# koppelpunkt.net
KiCad netlist of a schematic drawn in EAGLE
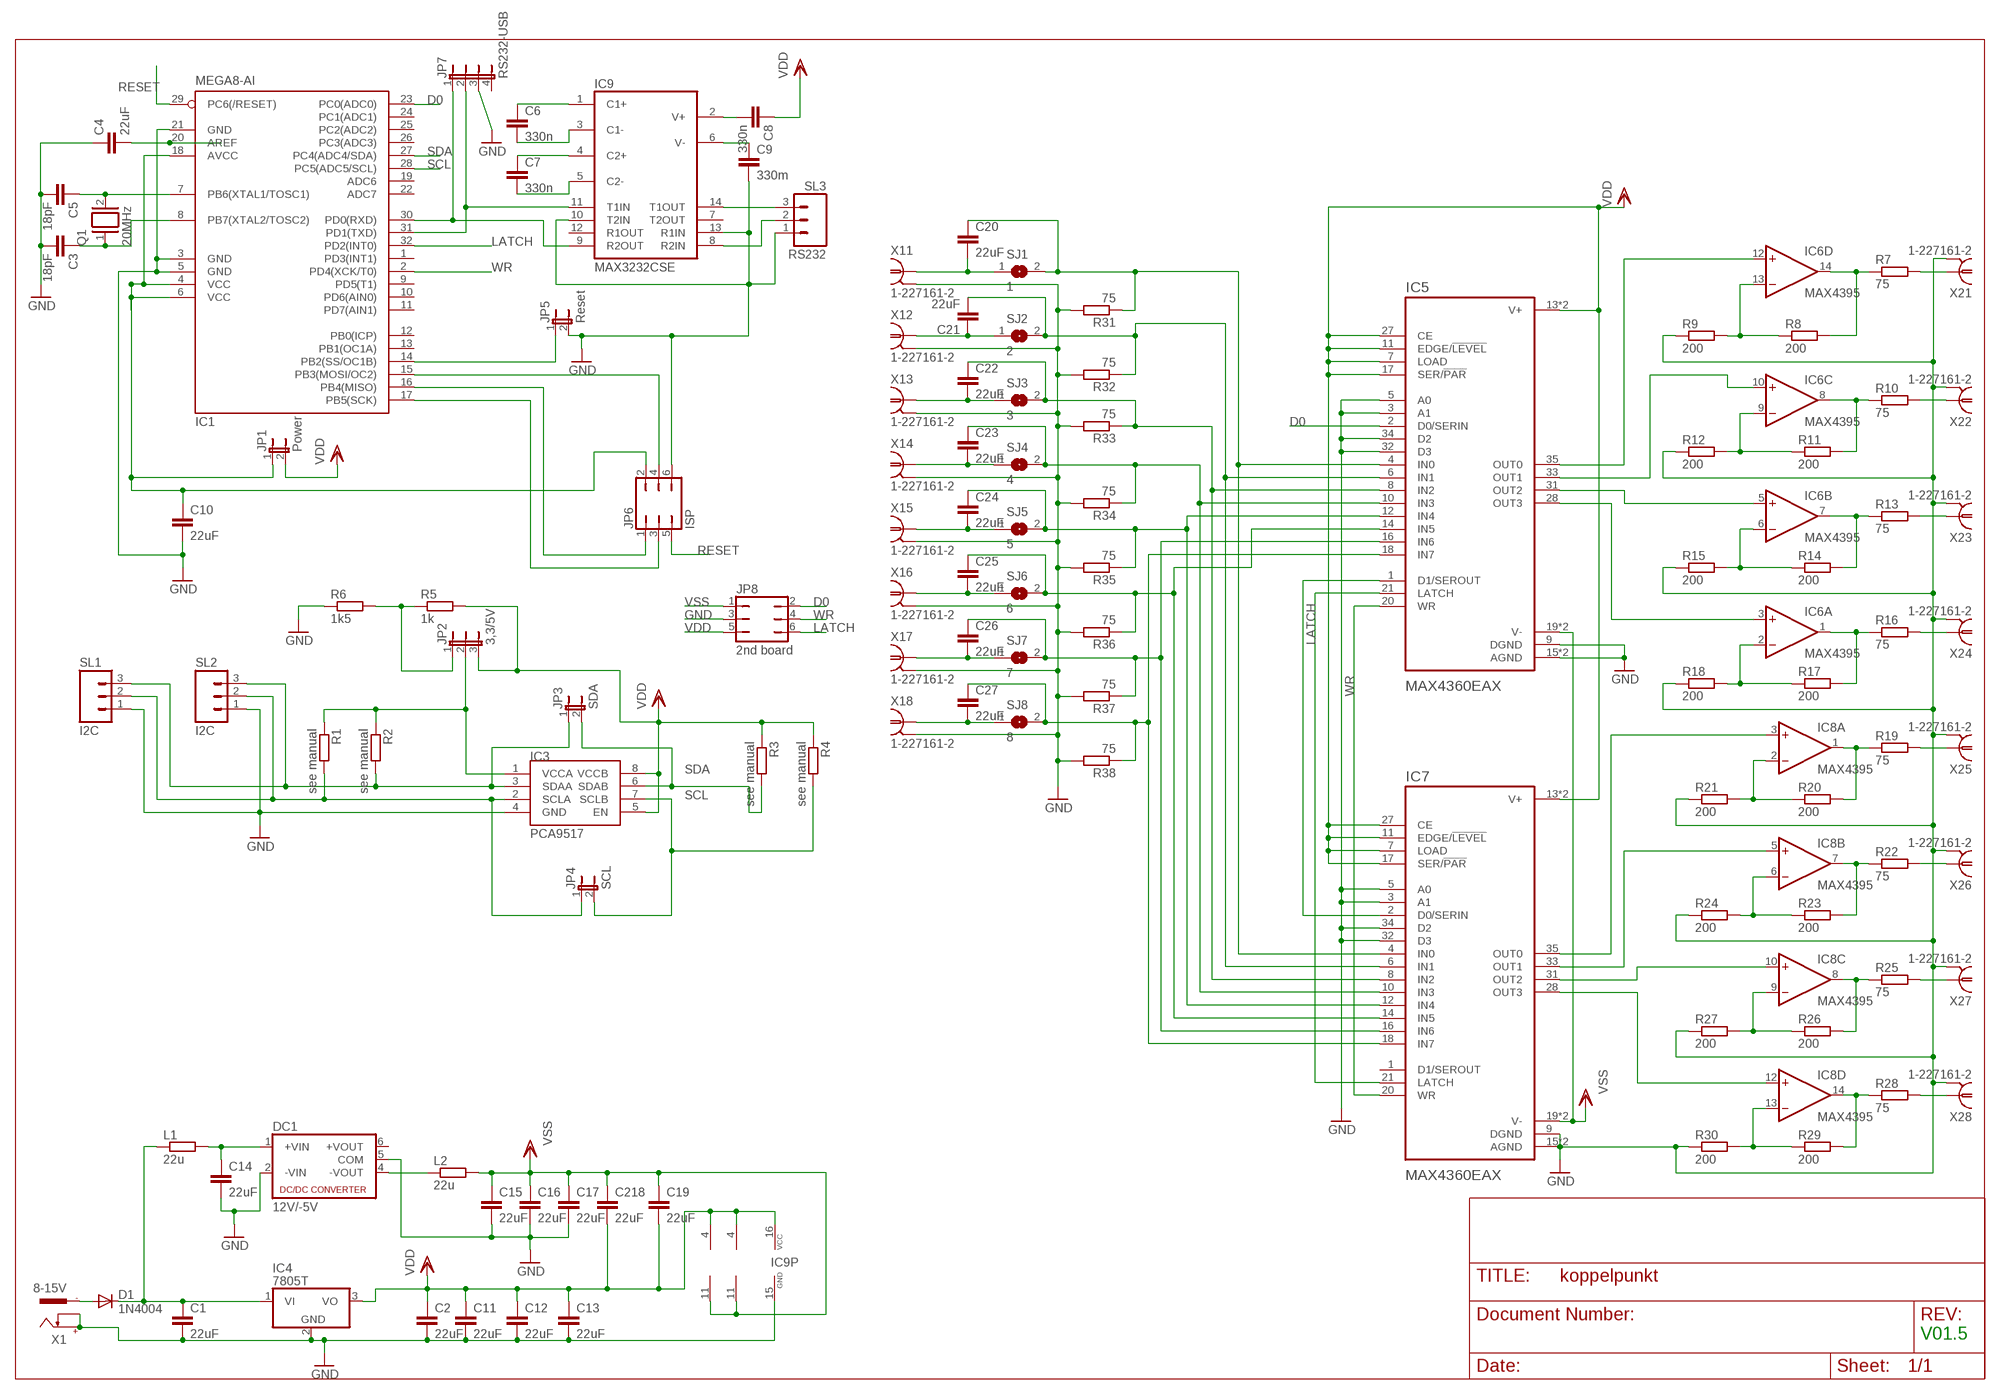
[diagram p0: schematic, sheet 1]

(export (version "E")
  (design (tool "Eeschema 10.0.6"))
  (components
    (comp (ref "C1")
      (value "22uF")
      (footprint "eagle-import:C1206")
      (libsource (lib "eagle-import") (part "C-EUC1206"))
    )
    (comp (ref "C2")
      (value "22uF")
      (footprint "eagle-import:C1206")
      (libsource (lib "eagle-import") (part "C-EUC1206"))
    )
    (comp (ref "C3")
      (value "18pF")
      (footprint "eagle-import:C025-025X050")
      (libsource (lib "eagle-import") (part "resistor_C-EU025-025X050"))
    )
    (comp (ref "C4")
      (value "22uF")
      (footprint "eagle-import:C1206")
      (libsource (lib "eagle-import") (part "C-EUC1206"))
    )
    (comp (ref "C5")
      (value "18pF")
      (footprint "eagle-import:C025-025X050")
      (libsource (lib "eagle-import") (part "resistor_C-EU025-025X050"))
    )
    (comp (ref "C6")
      (value "330n")
      (footprint "eagle-import:C1206")
      (libsource (lib "eagle-import") (part "C-EUC1206"))
    )
    (comp (ref "C7")
      (value "330n")
      (footprint "eagle-import:C1206")
      (libsource (lib "eagle-import") (part "C-EUC1206"))
    )
    (comp (ref "C8")
      (value "330n")
      (footprint "eagle-import:C1206")
      (libsource (lib "eagle-import") (part "C-EUC1206"))
    )
    (comp (ref "C9")
      (value "330m")
      (footprint "eagle-import:C1206")
      (libsource (lib "eagle-import") (part "C-EUC1206"))
    )
    (comp (ref "C10")
      (value "22uF")
      (footprint "eagle-import:C1206")
      (libsource (lib "eagle-import") (part "C-EUC1206"))
    )
    (comp (ref "C11")
      (value "22uF")
      (footprint "eagle-import:C1206")
      (libsource (lib "eagle-import") (part "C-EUC1206"))
    )
    (comp (ref "C12")
      (value "22uF")
      (footprint "eagle-import:C1206")
      (libsource (lib "eagle-import") (part "C-EUC1206"))
    )
    (comp (ref "C13")
      (value "22uF")
      (footprint "eagle-import:C1206")
      (libsource (lib "eagle-import") (part "C-EUC1206"))
    )
    (comp (ref "C14")
      (value "22uF")
      (footprint "eagle-import:C1206")
      (libsource (lib "eagle-import") (part "C-EUC1206"))
    )
    (comp (ref "C15")
      (value "22uF")
      (footprint "eagle-import:C1206")
      (libsource (lib "eagle-import") (part "C-EUC1206"))
    )
    (comp (ref "C16")
      (value "22uF")
      (footprint "eagle-import:C1206")
      (libsource (lib "eagle-import") (part "C-EUC1206"))
    )
    (comp (ref "C17")
      (value "22uF")
      (footprint "eagle-import:C1206")
      (libsource (lib "eagle-import") (part "C-EUC1206"))
    )
    (comp (ref "C19")
      (value "22uF")
      (footprint "eagle-import:C1206")
      (libsource (lib "eagle-import") (part "C-EUC1206"))
    )
    (comp (ref "C20")
      (value "22uF")
      (footprint "eagle-import:C1206")
      (libsource (lib "eagle-import") (part "C-EUC1206"))
    )
    (comp (ref "C21")
      (value "22uF")
      (footprint "eagle-import:C1206")
      (libsource (lib "eagle-import") (part "C-EUC1206"))
    )
    (comp (ref "C22")
      (value "22uF")
      (footprint "eagle-import:C1206")
      (libsource (lib "eagle-import") (part "C-EUC1206"))
    )
    (comp (ref "C23")
      (value "22uF")
      (footprint "eagle-import:C1206")
      (libsource (lib "eagle-import") (part "C-EUC1206"))
    )
    (comp (ref "C24")
      (value "22uF")
      (footprint "eagle-import:C1206")
      (libsource (lib "eagle-import") (part "C-EUC1206"))
    )
    (comp (ref "C25")
      (value "22uF")
      (footprint "eagle-import:C1206")
      (libsource (lib "eagle-import") (part "C-EUC1206"))
    )
    (comp (ref "C26")
      (value "22uF")
      (footprint "eagle-import:C1206")
      (libsource (lib "eagle-import") (part "C-EUC1206"))
    )
    (comp (ref "C27")
      (value "22uF")
      (footprint "eagle-import:C1206")
      (libsource (lib "eagle-import") (part "C-EUC1206"))
    )
    (comp (ref "C218")
      (value "22uF")
      (footprint "eagle-import:C1206")
      (libsource (lib "eagle-import") (part "C-EUC1206"))
    )
    (comp (ref "D1")
      (value "1N4004")
      (footprint "eagle-import:DO41-10")
      (libsource (lib "eagle-import") (part "1N4004"))
    )
    (comp (ref "DC1")
      (value "12V/-5V")
      (footprint "eagle-import:NMA")
      (fields (field (name "MF") "C & D TECHNOLOGIES, INC") (field (name "MPN") "NMA0515SC"))
      (libsource (lib "eagle-import") (part "NMA"))
    )
    (comp (ref "IC1")
      (value "MEGA8-AI")
      (footprint "eagle-import:TQFP32-08")
      (fields (field (name "MPN") "ATMEGA8-16AU"))
      (libsource (lib "eagle-import") (part "MEGA8-AI"))
    )
    (comp (ref "IC3")
      (value "PCA9517")
      (footprint "eagle-import:SO-08")
      (libsource (lib "eagle-import") (part "PCA9517"))
    )
    (comp (ref "IC4")
      (value "7805T")
      (footprint "eagle-import:TO220H")
      (libsource (lib "eagle-import") (part "78T05"))
    )
    (comp (ref "IC5")
      (value "MAX4360EAX")
      (footprint "eagle-import:SOP80P1030X264-36N")
      (fields (field (name "MF") "Maxim Integrated"))
      (libsource (lib "eagle-import") (part "MAX4360EAX"))
    )
    (comp (ref "IC6")
      (value "MAX4395")
      (footprint "eagle-import:SO14")
      (libsource (lib "eagle-import") (part "LM324D"))
    )
    (comp (ref "IC7")
      (value "MAX4360EAX")
      (footprint "eagle-import:SOP80P1030X264-36N")
      (fields (field (name "MF") "Maxim Integrated"))
      (libsource (lib "eagle-import") (part "MAX4360EAX"))
    )
    (comp (ref "IC8")
      (value "MAX4395")
      (footprint "eagle-import:SO14")
      (libsource (lib "eagle-import") (part "LM324D"))
    )
    (comp (ref "IC9")
      (value "MAX3232CSE")
      (footprint "eagle-import:SO16")
      (libsource (lib "eagle-import") (part "MAX3232SEC"))
    )
    (comp (ref "JP1")
      (value "Power")
      (footprint "eagle-import:JP1")
      (libsource (lib "eagle-import") (part "JP1E"))
    )
    (comp (ref "JP2")
      (value "3,3/5V")
      (footprint "eagle-import:JP2")
      (libsource (lib "eagle-import") (part "JP2E"))
    )
    (comp (ref "JP3")
      (value "SDA")
      (footprint "eagle-import:JP1")
      (libsource (lib "eagle-import") (part "JP1E"))
    )
    (comp (ref "JP4")
      (value "SCL")
      (footprint "eagle-import:JP1")
      (libsource (lib "eagle-import") (part "JP1E"))
    )
    (comp (ref "JP5")
      (value "Reset")
      (footprint "eagle-import:JP1")
      (libsource (lib "eagle-import") (part "JP1E"))
    )
    (comp (ref "JP6")
      (value "ISP")
      (footprint "eagle-import:JP3Q")
      (libsource (lib "eagle-import") (part "JP3Q"))
    )
    (comp (ref "JP7")
      (value "RS232-USB")
      (footprint "eagle-import:JP4")
      (libsource (lib "eagle-import") (part "JP4E"))
    )
    (comp (ref "JP8")
      (value "2nd board")
      (footprint "eagle-import:JP3Q")
      (libsource (lib "eagle-import") (part "JP3Q"))
    )
    (comp (ref "L1")
      (value "22u")
      (footprint "eagle-import:R6332")
      (libsource (lib "eagle-import") (part "resistor_R-EU_R6332"))
    )
    (comp (ref "L2")
      (value "22u")
      (footprint "eagle-import:R6332")
      (libsource (lib "eagle-import") (part "resistor_R-EU_R6332"))
    )
    (comp (ref "Q1")
      (value "20MHz")
      (footprint "eagle-import:QS")
      (libsource (lib "eagle-import") (part "XTAL/S"))
    )
    (comp (ref "R1")
      (value "see manual")
      (footprint "eagle-import:R1206")
      (libsource (lib "eagle-import") (part "resistor_R-EU_R1206"))
    )
    (comp (ref "R2")
      (value "see manual")
      (footprint "eagle-import:R1206")
      (libsource (lib "eagle-import") (part "resistor_R-EU_R1206"))
    )
    (comp (ref "R3")
      (value "see manual")
      (footprint "eagle-import:R1206")
      (libsource (lib "eagle-import") (part "resistor_R-EU_R1206"))
    )
    (comp (ref "R4")
      (value "see manual")
      (footprint "eagle-import:R1206")
      (libsource (lib "eagle-import") (part "resistor_R-EU_R1206"))
    )
    (comp (ref "R5")
      (value "1k")
      (footprint "eagle-import:R1206")
      (libsource (lib "eagle-import") (part "R-EU_R1206"))
    )
    (comp (ref "R6")
      (value "1k5")
      (footprint "eagle-import:R1206")
      (libsource (lib "eagle-import") (part "R-EU_R1206"))
    )
    (comp (ref "R7")
      (value "75")
      (footprint "eagle-import:R1206")
      (libsource (lib "eagle-import") (part "resistor_R-EU_R1206"))
    )
    (comp (ref "R8")
      (value "200")
      (footprint "eagle-import:R1206")
      (libsource (lib "eagle-import") (part "resistor_R-EU_R1206"))
    )
    (comp (ref "R9")
      (value "200")
      (footprint "eagle-import:M1206")
      (libsource (lib "eagle-import") (part "resistor_R-EU_M1206"))
    )
    (comp (ref "R10")
      (value "75")
      (footprint "eagle-import:R1206")
      (libsource (lib "eagle-import") (part "resistor_R-EU_R1206"))
    )
    (comp (ref "R11")
      (value "200")
      (footprint "eagle-import:R1206")
      (libsource (lib "eagle-import") (part "resistor_R-EU_R1206"))
    )
    (comp (ref "R12")
      (value "200")
      (footprint "eagle-import:R1206")
      (libsource (lib "eagle-import") (part "resistor_R-EU_R1206"))
    )
    (comp (ref "R13")
      (value "75")
      (footprint "eagle-import:R1206")
      (libsource (lib "eagle-import") (part "resistor_R-EU_R1206"))
    )
    (comp (ref "R14")
      (value "200")
      (footprint "eagle-import:R1206")
      (libsource (lib "eagle-import") (part "resistor_R-EU_R1206"))
    )
    (comp (ref "R15")
      (value "200")
      (footprint "eagle-import:R1206")
      (libsource (lib "eagle-import") (part "resistor_R-EU_R1206"))
    )
    (comp (ref "R16")
      (value "75")
      (footprint "eagle-import:R1206")
      (libsource (lib "eagle-import") (part "resistor_R-EU_R1206"))
    )
    (comp (ref "R17")
      (value "200")
      (footprint "eagle-import:R1206")
      (libsource (lib "eagle-import") (part "resistor_R-EU_R1206"))
    )
    (comp (ref "R18")
      (value "200")
      (footprint "eagle-import:R1206")
      (libsource (lib "eagle-import") (part "resistor_R-EU_R1206"))
    )
    (comp (ref "R19")
      (value "75")
      (footprint "eagle-import:R1206")
      (libsource (lib "eagle-import") (part "resistor_R-EU_R1206"))
    )
    (comp (ref "R20")
      (value "200")
      (footprint "eagle-import:R1206")
      (libsource (lib "eagle-import") (part "resistor_R-EU_R1206"))
    )
    (comp (ref "R21")
      (value "200")
      (footprint "eagle-import:R1206")
      (libsource (lib "eagle-import") (part "resistor_R-EU_R1206"))
    )
    (comp (ref "R22")
      (value "75")
      (footprint "eagle-import:R1206")
      (libsource (lib "eagle-import") (part "resistor_R-EU_R1206"))
    )
    (comp (ref "R23")
      (value "200")
      (footprint "eagle-import:R1206")
      (libsource (lib "eagle-import") (part "resistor_R-EU_R1206"))
    )
    (comp (ref "R24")
      (value "200")
      (footprint "eagle-import:R1206")
      (libsource (lib "eagle-import") (part "resistor_R-EU_R1206"))
    )
    (comp (ref "R25")
      (value "75")
      (footprint "eagle-import:R1206")
      (libsource (lib "eagle-import") (part "resistor_R-EU_R1206"))
    )
    (comp (ref "R26")
      (value "200")
      (footprint "eagle-import:R1206")
      (libsource (lib "eagle-import") (part "resistor_R-EU_R1206"))
    )
    (comp (ref "R27")
      (value "200")
      (footprint "eagle-import:R1206")
      (libsource (lib "eagle-import") (part "resistor_R-EU_R1206"))
    )
    (comp (ref "R28")
      (value "75")
      (footprint "eagle-import:R1206")
      (libsource (lib "eagle-import") (part "resistor_R-EU_R1206"))
    )
    (comp (ref "R29")
      (value "200")
      (footprint "eagle-import:R1206")
      (libsource (lib "eagle-import") (part "resistor_R-EU_R1206"))
    )
    (comp (ref "R30")
      (value "200")
      (footprint "eagle-import:R1206")
      (libsource (lib "eagle-import") (part "resistor_R-EU_R1206"))
    )
    (comp (ref "R31")
      (value "75")
      (footprint "eagle-import:R1206")
      (libsource (lib "eagle-import") (part "resistor_R-EU_R1206"))
    )
    (comp (ref "R32")
      (value "75")
      (footprint "eagle-import:R1206")
      (libsource (lib "eagle-import") (part "resistor_R-EU_R1206"))
    )
    (comp (ref "R33")
      (value "75")
      (footprint "eagle-import:R1206")
      (libsource (lib "eagle-import") (part "resistor_R-EU_R1206"))
    )
    (comp (ref "R34")
      (value "75")
      (footprint "eagle-import:R1206")
      (libsource (lib "eagle-import") (part "resistor_R-EU_R1206"))
    )
    (comp (ref "R35")
      (value "75")
      (footprint "eagle-import:R1206")
      (libsource (lib "eagle-import") (part "resistor_R-EU_R1206"))
    )
    (comp (ref "R36")
      (value "75")
      (footprint "eagle-import:R1206")
      (libsource (lib "eagle-import") (part "resistor_R-EU_R1206"))
    )
    (comp (ref "R37")
      (value "75")
      (footprint "eagle-import:R1206")
      (libsource (lib "eagle-import") (part "resistor_R-EU_R1206"))
    )
    (comp (ref "R38")
      (value "75")
      (footprint "eagle-import:R1206")
      (libsource (lib "eagle-import") (part "resistor_R-EU_R1206"))
    )
    (comp (ref "SJ1") (value "1") (footprint "eagle-import:SJ") (libsource (lib "eagle-import") (part "SJ")))
    (comp (ref "SJ2") (value "2") (footprint "eagle-import:SJ") (libsource (lib "eagle-import") (part "SJ")))
    (comp (ref "SJ3") (value "3") (footprint "eagle-import:SJ") (libsource (lib "eagle-import") (part "SJ")))
    (comp (ref "SJ4") (value "4") (footprint "eagle-import:SJ") (libsource (lib "eagle-import") (part "SJ")))
    (comp (ref "SJ5") (value "5") (footprint "eagle-import:SJ") (libsource (lib "eagle-import") (part "SJ")))
    (comp (ref "SJ6") (value "6") (footprint "eagle-import:SJ") (libsource (lib "eagle-import") (part "SJ")))
    (comp (ref "SJ7") (value "7") (footprint "eagle-import:SJ") (libsource (lib "eagle-import") (part "SJ")))
    (comp (ref "SJ8") (value "8") (footprint "eagle-import:SJ") (libsource (lib "eagle-import") (part "SJ")))
    (comp (ref "SL1")
      (value "I2C")
      (footprint "eagle-import:03P")
      (libsource (lib "eagle-import") (part "M03"))
    )
    (comp (ref "SL2")
      (value "I2C")
      (footprint "eagle-import:03P")
      (libsource (lib "eagle-import") (part "M03"))
    )
    (comp (ref "SL3")
      (value "RS232")
      (footprint "eagle-import:03P")
      (libsource (lib "eagle-import") (part "M03"))
    )
    (comp (ref "X1")
      (value "8-15V")
      (footprint "eagle-import:737992-5")
      (libsource (lib "eagle-import") (part "737992-55"))
    )
    (comp (ref "X11")
      (value "1-227161-2")
      (footprint "eagle-import:AMP_227161")
      (libsource (lib "eagle-import") (part "?2271611--2"))
    )
    (comp (ref "X12")
      (value "1-227161-2")
      (footprint "eagle-import:AMP_227161")
      (libsource (lib "eagle-import") (part "?2271611--2"))
    )
    (comp (ref "X13")
      (value "1-227161-2")
      (footprint "eagle-import:AMP_227161")
      (libsource (lib "eagle-import") (part "?2271611--2"))
    )
    (comp (ref "X14")
      (value "1-227161-2")
      (footprint "eagle-import:AMP_227161")
      (libsource (lib "eagle-import") (part "?2271611--2"))
    )
    (comp (ref "X15")
      (value "1-227161-2")
      (footprint "eagle-import:AMP_227161")
      (libsource (lib "eagle-import") (part "?2271611--2"))
    )
    (comp (ref "X16")
      (value "1-227161-2")
      (footprint "eagle-import:AMP_227161")
      (libsource (lib "eagle-import") (part "?2271611--2"))
    )
    (comp (ref "X17")
      (value "1-227161-2")
      (footprint "eagle-import:AMP_227161")
      (libsource (lib "eagle-import") (part "?2271611--2"))
    )
    (comp (ref "X18")
      (value "1-227161-2")
      (footprint "eagle-import:AMP_227161")
      (libsource (lib "eagle-import") (part "?2271611--2"))
    )
    (comp (ref "X21")
      (value "1-227161-2")
      (footprint "eagle-import:AMP_227161")
      (libsource (lib "eagle-import") (part "?2271611--2"))
    )
    (comp (ref "X22")
      (value "1-227161-2")
      (footprint "eagle-import:AMP_227161")
      (libsource (lib "eagle-import") (part "?2271611--2"))
    )
    (comp (ref "X23")
      (value "1-227161-2")
      (footprint "eagle-import:AMP_227161")
      (libsource (lib "eagle-import") (part "?2271611--2"))
    )
    (comp (ref "X24")
      (value "1-227161-2")
      (footprint "eagle-import:AMP_227161")
      (libsource (lib "eagle-import") (part "?2271611--2"))
    )
    (comp (ref "X25")
      (value "1-227161-2")
      (footprint "eagle-import:AMP_227161")
      (libsource (lib "eagle-import") (part "?2271611--2"))
    )
    (comp (ref "X26")
      (value "1-227161-2")
      (footprint "eagle-import:AMP_227161")
      (libsource (lib "eagle-import") (part "?2271611--2"))
    )
    (comp (ref "X27")
      (value "1-227161-2")
      (footprint "eagle-import:AMP_227161")
      (libsource (lib "eagle-import") (part "?2271611--2"))
    )
    (comp (ref "X28")
      (value "1-227161-2")
      (footprint "eagle-import:AMP_227161")
      (libsource (lib "eagle-import") (part "?2271611--2"))
    )
  )
  (nets
    (net (code "1") (name "/D0") (class "Default")
      (node (ref "IC1") (pin "23") (pinfunction "PC0(ADC0)_23") (pintype "bidirectional"))
      (node (ref "IC5") (pin "2") (pinfunction "D0/SERIN_2") (pintype "input"))
      (node (ref "JP8") (pin "2") (pinfunction "2_2") (pintype "passive"))
    )
    (net (code "2") (name "/LATCH") (class "Default")
      (node (ref "IC1") (pin "32") (pinfunction "PD2(INT0)_32") (pintype "bidirectional"))
      (node (ref "IC5") (pin "21") (pinfunction "LATCH_21") (pintype "bidirectional"))
      (node (ref "IC7") (pin "21") (pinfunction "LATCH_21") (pintype "bidirectional"))
      (node (ref "JP8") (pin "6") (pinfunction "6_6") (pintype "passive"))
    )
    (net (code "3") (name "/RESET") (class "Default")
      (node (ref "IC1") (pin "29") (pinfunction "PC6(/RESET)_29") (pintype "bidirectional"))
      (node (ref "JP6") (pin "5") (pinfunction "5_5") (pintype "passive"))
    )
    (net (code "4") (name "/SCL") (class "Default")
      (node (ref "IC1") (pin "28") (pinfunction "PC5(ADC5/SCL)_28") (pintype "bidirectional"))
      (node (ref "IC3") (pin "7") (pinfunction "SCLB_7") (pintype "bidirectional"))
      (node (ref "JP4") (pin "2") (pinfunction "2_2") (pintype "passive"))
      (node (ref "R4") (pin "2") (pinfunction "2_2") (pintype "passive"))
    )
    (net (code "5") (name "/SDA") (class "Default")
      (node (ref "IC1") (pin "27") (pinfunction "PC4(ADC4/SDA)_27") (pintype "bidirectional"))
      (node (ref "IC3") (pin "6") (pinfunction "SDAB_6") (pintype "bidirectional"))
      (node (ref "JP3") (pin "2") (pinfunction "2_2") (pintype "passive"))
      (node (ref "R3") (pin "2") (pinfunction "2_2") (pintype "passive"))
    )
    (net (code "6") (name "/WR") (class "Default")
      (node (ref "IC1") (pin "2") (pinfunction "PD4(XCK/T0)_2") (pintype "bidirectional"))
      (node (ref "IC5") (pin "20") (pinfunction "WR_20") (pintype "bidirectional"))
      (node (ref "IC7") (pin "20") (pinfunction "WR_20") (pintype "bidirectional"))
      (node (ref "JP8") (pin "4") (pinfunction "4_4") (pintype "passive"))
    )
    (net (code "7") (name "GND") (class "Default")
      (node (ref "C1") (pin "2") (pinfunction "2_2") (pintype "passive"))
      (node (ref "C10") (pin "2") (pinfunction "2_2") (pintype "passive"))
      (node (ref "C11") (pin "2") (pinfunction "2_2") (pintype "passive"))
      (node (ref "C12") (pin "2") (pinfunction "2_2") (pintype "passive"))
      (node (ref "C13") (pin "2") (pinfunction "2_2") (pintype "passive"))
      (node (ref "C14") (pin "2") (pinfunction "2_2") (pintype "passive"))
      (node (ref "C15") (pin "2") (pinfunction "2_2") (pintype "passive"))
      (node (ref "C16") (pin "2") (pinfunction "2_2") (pintype "passive"))
      (node (ref "C17") (pin "2") (pinfunction "2_2") (pintype "passive"))
      (node (ref "C2") (pin "2") (pinfunction "2_2") (pintype "passive"))
      (node (ref "C3") (pin "2") (pinfunction "2_2") (pintype "passive"))
      (node (ref "C4") (pin "1") (pinfunction "1_1") (pintype "passive"))
      (node (ref "C5") (pin "2") (pinfunction "2_2") (pintype "passive"))
      (node (ref "C9") (pin "2") (pinfunction "2_2") (pintype "passive"))
      (node (ref "DC1") (pin "2") (pinfunction "-VIN_2") (pintype "passive"))
      (node (ref "DC1") (pin "5") (pinfunction "COM_5") (pintype "passive"))
      (node (ref "IC1") (pin "21") (pinfunction "GND_21") (pintype "power_in"))
      (node (ref "IC1") (pin "3") (pinfunction "GND_3") (pintype "power_in"))
      (node (ref "IC1") (pin "5") (pinfunction "GND_5") (pintype "power_in"))
      (node (ref "IC3") (pin "4") (pinfunction "GND_4") (pintype "bidirectional"))
      (node (ref "IC4") (pin "2") (pinfunction "GND_2") (pintype "passive"))
      (node (ref "IC5") (pin "15") (pinfunction "AGND_15") (pintype "power_in"))
      (node (ref "IC5") (pin "29") (pinfunction "AGND_29") (pintype "power_in"))
      (node (ref "IC5") (pin "3") (pinfunction "A1_3") (pintype "input"))
      (node (ref "IC5") (pin "32") (pinfunction "D3_32") (pintype "input"))
      (node (ref "IC5") (pin "34") (pinfunction "D2_34") (pintype "input"))
      (node (ref "IC5") (pin "5") (pinfunction "A0_5") (pintype "input"))
      (node (ref "IC5") (pin "9") (pinfunction "DGND_9") (pintype "power_in"))
      (node (ref "IC7") (pin "15") (pinfunction "AGND_15") (pintype "power_in"))
      (node (ref "IC7") (pin "29") (pinfunction "AGND_29") (pintype "power_in"))
      (node (ref "IC7") (pin "3") (pinfunction "A1_3") (pintype "input"))
      (node (ref "IC7") (pin "32") (pinfunction "D3_32") (pintype "input"))
      (node (ref "IC7") (pin "34") (pinfunction "D2_34") (pintype "input"))
      (node (ref "IC7") (pin "5") (pinfunction "A0_5") (pintype "input"))
      (node (ref "IC7") (pin "9") (pinfunction "DGND_9") (pintype "power_in"))
      (node (ref "IC9") (pin "10") (pinfunction "T2IN_10") (pintype "input"))
      (node (ref "IC9") (pin "13") (pinfunction "R1IN_13") (pintype "input"))
      (node (ref "IC9") (pin "15") (pinfunction "GND_15") (pintype "power_in"))
      (node (ref "JP5") (pin "2") (pinfunction "2_2") (pintype "passive"))
      (node (ref "JP6") (pin "6") (pinfunction "6_6") (pintype "passive"))
      (node (ref "JP7") (pin "3") (pinfunction "3_3") (pintype "passive"))
      (node (ref "JP8") (pin "3") (pinfunction "3_3") (pintype "passive"))
      (node (ref "R12") (pin "1") (pinfunction "1_1") (pintype "passive"))
      (node (ref "R15") (pin "1") (pinfunction "1_1") (pintype "passive"))
      (node (ref "R18") (pin "1") (pinfunction "1_1") (pintype "passive"))
      (node (ref "R21") (pin "1") (pinfunction "1_1") (pintype "passive"))
      (node (ref "R24") (pin "1") (pinfunction "1_1") (pintype "passive"))
      (node (ref "R27") (pin "1") (pinfunction "1_1") (pintype "passive"))
      (node (ref "R30") (pin "1") (pinfunction "1_1") (pintype "passive"))
      (node (ref "R31") (pin "2") (pinfunction "2_2") (pintype "passive"))
      (node (ref "R32") (pin "2") (pinfunction "2_2") (pintype "passive"))
      (node (ref "R33") (pin "2") (pinfunction "2_2") (pintype "passive"))
      (node (ref "R34") (pin "2") (pinfunction "2_2") (pintype "passive"))
      (node (ref "R35") (pin "2") (pinfunction "2_2") (pintype "passive"))
      (node (ref "R36") (pin "2") (pinfunction "2_2") (pintype "passive"))
      (node (ref "R37") (pin "2") (pinfunction "2_2") (pintype "passive"))
      (node (ref "R38") (pin "2") (pinfunction "2_2") (pintype "passive"))
      (node (ref "R6") (pin "1") (pinfunction "1_1") (pintype "passive"))
      (node (ref "R9") (pin "1") (pinfunction "1_1") (pintype "passive"))
      (node (ref "SL1") (pin "1") (pinfunction "1_1") (pintype "passive"))
      (node (ref "SL2") (pin "1") (pinfunction "1_1") (pintype "passive"))
      (node (ref "SL3") (pin "1") (pinfunction "1_1") (pintype "passive"))
      (node (ref "X1") (pin "+") (pinfunction "+_+") (pintype "passive"))
      (node (ref "X1") (pin "K") (pinfunction "K_K") (pintype "passive"))
      (node (ref "X11") (pin "2") (pinfunction "2_2") (pintype "passive"))
      (node (ref "X12") (pin "2") (pinfunction "2_2") (pintype "passive"))
      (node (ref "X13") (pin "2") (pinfunction "2_2") (pintype "passive"))
      (node (ref "X14") (pin "2") (pinfunction "2_2") (pintype "passive"))
      (node (ref "X15") (pin "2") (pinfunction "2_2") (pintype "passive"))
      (node (ref "X16") (pin "2") (pinfunction "2_2") (pintype "passive"))
      (node (ref "X17") (pin "2") (pinfunction "2_2") (pintype "passive"))
      (node (ref "X18") (pin "2") (pinfunction "2_2") (pintype "passive"))
      (node (ref "X21") (pin "2") (pinfunction "2_2") (pintype "passive"))
      (node (ref "X22") (pin "2") (pinfunction "2_2") (pintype "passive"))
      (node (ref "X23") (pin "2") (pinfunction "2_2") (pintype "passive"))
      (node (ref "X24") (pin "2") (pinfunction "2_2") (pintype "passive"))
      (node (ref "X25") (pin "2") (pinfunction "2_2") (pintype "passive"))
      (node (ref "X26") (pin "2") (pinfunction "2_2") (pintype "passive"))
      (node (ref "X27") (pin "2") (pinfunction "2_2") (pintype "passive"))
      (node (ref "X28") (pin "2") (pinfunction "2_2") (pintype "passive"))
    )
    (net (code "8") (name "Net-(C20-Pad2)") (class "Default")
      (node (ref "C20") (pin "2") (pinfunction "2_2") (pintype "passive"))
      (node (ref "SJ1") (pin "1") (pinfunction "1_1") (pintype "passive"))
      (node (ref "X11") (pin "1") (pinfunction "1_1") (pintype "passive"))
    )
    (net (code "9") (name "Net-(C21-Pad1)") (class "Default")
      (node (ref "C21") (pin "1") (pinfunction "1_1") (pintype "passive"))
      (node (ref "SJ2") (pin "1") (pinfunction "1_1") (pintype "passive"))
      (node (ref "X12") (pin "1") (pinfunction "1_1") (pintype "passive"))
    )
    (net (code "10") (name "Net-(C22-Pad2)") (class "Default")
      (node (ref "C22") (pin "2") (pinfunction "2_2") (pintype "passive"))
      (node (ref "SJ3") (pin "1") (pinfunction "1_1") (pintype "passive"))
      (node (ref "X13") (pin "1") (pinfunction "1_1") (pintype "passive"))
    )
    (net (code "11") (name "Net-(C23-Pad2)") (class "Default")
      (node (ref "C23") (pin "2") (pinfunction "2_2") (pintype "passive"))
      (node (ref "SJ4") (pin "1") (pinfunction "1_1") (pintype "passive"))
      (node (ref "X14") (pin "1") (pinfunction "1_1") (pintype "passive"))
    )
    (net (code "12") (name "Net-(C24-Pad2)") (class "Default")
      (node (ref "C24") (pin "2") (pinfunction "2_2") (pintype "passive"))
      (node (ref "SJ5") (pin "1") (pinfunction "1_1") (pintype "passive"))
      (node (ref "X15") (pin "1") (pinfunction "1_1") (pintype "passive"))
    )
    (net (code "13") (name "Net-(C25-Pad2)") (class "Default")
      (node (ref "C25") (pin "2") (pinfunction "2_2") (pintype "passive"))
      (node (ref "SJ6") (pin "1") (pinfunction "1_1") (pintype "passive"))
      (node (ref "X16") (pin "1") (pinfunction "1_1") (pintype "passive"))
    )
    (net (code "14") (name "Net-(C26-Pad2)") (class "Default")
      (node (ref "C26") (pin "2") (pinfunction "2_2") (pintype "passive"))
      (node (ref "SJ7") (pin "1") (pinfunction "1_1") (pintype "passive"))
      (node (ref "X17") (pin "1") (pinfunction "1_1") (pintype "passive"))
    )
    (net (code "15") (name "Net-(C27-Pad2)") (class "Default")
      (node (ref "C27") (pin "2") (pinfunction "2_2") (pintype "passive"))
      (node (ref "SJ8") (pin "1") (pinfunction "1_1") (pintype "passive"))
      (node (ref "X18") (pin "1") (pinfunction "1_1") (pintype "passive"))
    )
    (net (code "16") (name "Net-(D1-PadA)") (class "Default")
      (node (ref "D1") (pin "A") (pinfunction "A_A") (pintype "passive"))
      (node (ref "X1") (pin "-1") (pinfunction "-1_-1") (pintype "passive"))
    )
    (net (code "17") (name "Net-(DC1-+VIN)") (class "Default")
      (node (ref "C14") (pin "1") (pinfunction "1_1") (pintype "passive"))
      (node (ref "DC1") (pin "1") (pinfunction "+VIN_1") (pintype "passive"))
      (node (ref "L1") (pin "2") (pinfunction "2_2") (pintype "passive"))
    )
    (net (code "18") (name "Net-(DC1--VOUT)") (class "Default")
      (node (ref "DC1") (pin "4") (pinfunction "-VOUT_4") (pintype "passive"))
      (node (ref "L2") (pin "1") (pinfunction "1_1") (pintype "passive"))
    )
    (net (code "19") (name "Net-(IC1-AREF)") (class "Default")
      (node (ref "C4") (pin "2") (pinfunction "2_2") (pintype "passive"))
      (node (ref "IC1") (pin "20") (pinfunction "AREF_20") (pintype "passive"))
    )
    (net (code "20") (name "Net-(IC1-AVCC)") (class "Default")
      (node (ref "C10") (pin "1") (pinfunction "1_1") (pintype "passive"))
      (node (ref "IC1") (pin "18") (pinfunction "AVCC_18") (pintype "power_in"))
      (node (ref "IC1") (pin "4") (pinfunction "VCC_4") (pintype "power_in"))
      (node (ref "IC1") (pin "6") (pinfunction "VCC_6") (pintype "power_in"))
      (node (ref "JP1") (pin "1") (pinfunction "1_1") (pintype "passive"))
      (node (ref "JP6") (pin "2") (pinfunction "2_2") (pintype "passive"))
    )
    (net (code "21") (name "Net-(IC1-PB2(SS{slash}OC1B))") (class "Default")
      (node (ref "IC1") (pin "14") (pinfunction "PB2(SS/OC1B)_14") (pintype "bidirectional"))
      (node (ref "JP5") (pin "1") (pinfunction "1_1") (pintype "passive"))
    )
    (net (code "22") (name "Net-(IC1-PB3(MOSI{slash}OC2))") (class "Default")
      (node (ref "IC1") (pin "15") (pinfunction "PB3(MOSI/OC2)_15") (pintype "bidirectional"))
      (node (ref "JP6") (pin "4") (pinfunction "4_4") (pintype "passive"))
    )
    (net (code "23") (name "Net-(IC1-PB4(MISO))") (class "Default")
      (node (ref "IC1") (pin "16") (pinfunction "PB4(MISO)_16") (pintype "bidirectional"))
      (node (ref "JP6") (pin "1") (pinfunction "1_1") (pintype "passive"))
    )
    (net (code "24") (name "Net-(IC1-PB5(SCK))") (class "Default")
      (node (ref "IC1") (pin "17") (pinfunction "PB5(SCK)_17") (pintype "bidirectional"))
      (node (ref "JP6") (pin "3") (pinfunction "3_3") (pintype "passive"))
    )
    (net (code "25") (name "Net-(IC1-PB6(XTAL1{slash}TOSC1))") (class "Default")
      (node (ref "C5") (pin "1") (pinfunction "1_1") (pintype "passive"))
      (node (ref "IC1") (pin "7") (pinfunction "PB6(XTAL1/TOSC1)_7") (pintype "bidirectional"))
      (node (ref "Q1") (pin "2") (pinfunction "2_2") (pintype "passive"))
    )
    (net (code "26") (name "Net-(IC1-PB7(XTAL2{slash}TOSC2))") (class "Default")
      (node (ref "C3") (pin "1") (pinfunction "1_1") (pintype "passive"))
      (node (ref "IC1") (pin "8") (pinfunction "PB7(XTAL2/TOSC2)_8") (pintype "bidirectional"))
      (node (ref "Q1") (pin "1") (pinfunction "1_1") (pintype "passive"))
    )
    (net (code "27") (name "Net-(IC1-PD0(RXD))") (class "Default")
      (node (ref "IC1") (pin "30") (pinfunction "PD0(RXD)_30") (pintype "bidirectional"))
      (node (ref "IC9") (pin "9") (pinfunction "R2OUT_9") (pintype "output"))
      (node (ref "JP7") (pin "1") (pinfunction "1_1") (pintype "passive"))
    )
    (net (code "28") (name "Net-(IC1-PD1(TXD))") (class "Default")
      (node (ref "IC1") (pin "31") (pinfunction "PD1(TXD)_31") (pintype "bidirectional"))
      (node (ref "IC9") (pin "11") (pinfunction "T1IN_11") (pintype "input"))
      (node (ref "JP7") (pin "2") (pinfunction "2_2") (pintype "passive"))
    )
    (net (code "29") (name "Net-(IC3-SCLA)") (class "Default")
      (node (ref "IC3") (pin "2") (pinfunction "SCLA_2") (pintype "bidirectional"))
      (node (ref "JP4") (pin "1") (pinfunction "1_1") (pintype "passive"))
      (node (ref "R1") (pin "2") (pinfunction "2_2") (pintype "passive"))
      (node (ref "SL1") (pin "2") (pinfunction "2_2") (pintype "passive"))
      (node (ref "SL2") (pin "2") (pinfunction "2_2") (pintype "passive"))
    )
    (net (code "30") (name "Net-(IC3-SDAA)") (class "Default")
      (node (ref "IC3") (pin "3") (pinfunction "SDAA_3") (pintype "bidirectional"))
      (node (ref "JP3") (pin "1") (pinfunction "1_1") (pintype "passive"))
      (node (ref "R2") (pin "2") (pinfunction "2_2") (pintype "passive"))
      (node (ref "SL1") (pin "3") (pinfunction "3_3") (pintype "passive"))
      (node (ref "SL2") (pin "3") (pinfunction "3_3") (pintype "passive"))
    )
    (net (code "31") (name "Net-(IC3-VCCA)") (class "Default")
      (node (ref "IC3") (pin "1") (pinfunction "VCCA_1") (pintype "bidirectional"))
      (node (ref "JP2") (pin "2") (pinfunction "2_2") (pintype "passive"))
      (node (ref "R1") (pin "1") (pinfunction "1_1") (pintype "passive"))
      (node (ref "R2") (pin "1") (pinfunction "1_1") (pintype "passive"))
    )
    (net (code "32") (name "Net-(IC4-VI)") (class "Default")
      (node (ref "C1") (pin "1") (pinfunction "1_1") (pintype "passive"))
      (node (ref "D1") (pin "C") (pinfunction "C_C") (pintype "passive"))
      (node (ref "IC4") (pin "1") (pinfunction "VI_1") (pintype "input"))
      (node (ref "L1") (pin "1") (pinfunction "1_1") (pintype "passive"))
    )
    (net (code "33") (name "Net-(IC5-D1{slash}SEROUT)") (class "Default")
      (node (ref "IC5") (pin "1") (pinfunction "D1/SEROUT_1") (pintype "bidirectional"))
      (node (ref "IC7") (pin "2") (pinfunction "D0/SERIN_2") (pintype "input"))
    )
    (net (code "34") (name "Net-(IC5-IN0)") (class "Default")
      (node (ref "C20") (pin "1") (pinfunction "1_1") (pintype "passive"))
      (node (ref "IC5") (pin "4") (pinfunction "IN0_4") (pintype "input"))
      (node (ref "IC7") (pin "4") (pinfunction "IN0_4") (pintype "input"))
      (node (ref "R31") (pin "1") (pinfunction "1_1") (pintype "passive"))
      (node (ref "SJ1") (pin "2") (pinfunction "2_2") (pintype "passive"))
    )
    (net (code "35") (name "Net-(IC5-IN1)") (class "Default")
      (node (ref "C21") (pin "2") (pinfunction "2_2") (pintype "passive"))
      (node (ref "IC5") (pin "6") (pinfunction "IN1_6") (pintype "input"))
      (node (ref "IC7") (pin "6") (pinfunction "IN1_6") (pintype "input"))
      (node (ref "R32") (pin "1") (pinfunction "1_1") (pintype "passive"))
      (node (ref "SJ2") (pin "2") (pinfunction "2_2") (pintype "passive"))
    )
    (net (code "36") (name "Net-(IC5-IN2)") (class "Default")
      (node (ref "C22") (pin "1") (pinfunction "1_1") (pintype "passive"))
      (node (ref "IC5") (pin "8") (pinfunction "IN2_8") (pintype "input"))
      (node (ref "IC7") (pin "8") (pinfunction "IN2_8") (pintype "input"))
      (node (ref "R33") (pin "1") (pinfunction "1_1") (pintype "passive"))
      (node (ref "SJ3") (pin "2") (pinfunction "2_2") (pintype "passive"))
    )
    (net (code "37") (name "Net-(IC5-IN3)") (class "Default")
      (node (ref "C23") (pin "1") (pinfunction "1_1") (pintype "passive"))
      (node (ref "IC5") (pin "10") (pinfunction "IN3_10") (pintype "input"))
      (node (ref "IC7") (pin "10") (pinfunction "IN3_10") (pintype "input"))
      (node (ref "R34") (pin "1") (pinfunction "1_1") (pintype "passive"))
      (node (ref "SJ4") (pin "2") (pinfunction "2_2") (pintype "passive"))
    )
    (net (code "38") (name "Net-(IC5-IN4)") (class "Default")
      (node (ref "C24") (pin "1") (pinfunction "1_1") (pintype "passive"))
      (node (ref "IC5") (pin "12") (pinfunction "IN4_12") (pintype "input"))
      (node (ref "IC7") (pin "12") (pinfunction "IN4_12") (pintype "input"))
      (node (ref "R35") (pin "1") (pinfunction "1_1") (pintype "passive"))
      (node (ref "SJ5") (pin "2") (pinfunction "2_2") (pintype "passive"))
    )
    (net (code "39") (name "Net-(IC5-IN5)") (class "Default")
      (node (ref "C25") (pin "1") (pinfunction "1_1") (pintype "passive"))
      (node (ref "IC5") (pin "14") (pinfunction "IN5_14") (pintype "input"))
      (node (ref "IC7") (pin "14") (pinfunction "IN5_14") (pintype "input"))
      (node (ref "R36") (pin "1") (pinfunction "1_1") (pintype "passive"))
      (node (ref "SJ6") (pin "2") (pinfunction "2_2") (pintype "passive"))
    )
    (net (code "40") (name "Net-(IC5-IN6)") (class "Default")
      (node (ref "C26") (pin "1") (pinfunction "1_1") (pintype "passive"))
      (node (ref "IC5") (pin "16") (pinfunction "IN6_16") (pintype "input"))
      (node (ref "IC7") (pin "16") (pinfunction "IN6_16") (pintype "input"))
      (node (ref "R37") (pin "1") (pinfunction "1_1") (pintype "passive"))
      (node (ref "SJ7") (pin "2") (pinfunction "2_2") (pintype "passive"))
    )
    (net (code "41") (name "Net-(IC5-IN7)") (class "Default")
      (node (ref "C27") (pin "1") (pinfunction "1_1") (pintype "passive"))
      (node (ref "IC5") (pin "18") (pinfunction "IN7_18") (pintype "input"))
      (node (ref "IC7") (pin "18") (pinfunction "IN7_18") (pintype "input"))
      (node (ref "R38") (pin "1") (pinfunction "1_1") (pintype "passive"))
      (node (ref "SJ8") (pin "2") (pinfunction "2_2") (pintype "passive"))
    )
    (net (code "42") (name "Net-(IC5-OUT0)") (class "Default")
      (node (ref "IC5") (pin "35") (pinfunction "OUT0_35") (pintype "output"))
      (node (ref "IC6") (pin "12") (pinfunction "+IN_12") (pintype "input"))
    )
    (net (code "43") (name "Net-(IC5-OUT1)") (class "Default")
      (node (ref "IC5") (pin "33") (pinfunction "OUT1_33") (pintype "output"))
      (node (ref "IC6") (pin "10") (pinfunction "+IN_10") (pintype "input"))
    )
    (net (code "44") (name "Net-(IC5-OUT2)") (class "Default")
      (node (ref "IC5") (pin "31") (pinfunction "OUT2_31") (pintype "output"))
      (node (ref "IC6") (pin "5") (pinfunction "+IN_5") (pintype "input"))
    )
    (net (code "45") (name "Net-(IC5-OUT3)") (class "Default")
      (node (ref "IC5") (pin "28") (pinfunction "OUT3_28") (pintype "output"))
      (node (ref "IC6") (pin "3") (pinfunction "+IN_3") (pintype "input"))
    )
    (net (code "46") (name "Net-(IC6A--IN)") (class "Default")
      (node (ref "IC6") (pin "2") (pinfunction "-IN_2") (pintype "input"))
      (node (ref "R17") (pin "1") (pinfunction "1_1") (pintype "passive"))
      (node (ref "R18") (pin "2") (pinfunction "2_2") (pintype "passive"))
    )
    (net (code "47") (name "Net-(IC6A-OUT)") (class "Default")
      (node (ref "IC6") (pin "1") (pinfunction "OUT_1") (pintype "output"))
      (node (ref "R16") (pin "1") (pinfunction "1_1") (pintype "passive"))
      (node (ref "R17") (pin "2") (pinfunction "2_2") (pintype "passive"))
    )
    (net (code "48") (name "Net-(IC6B--IN)") (class "Default")
      (node (ref "IC6") (pin "6") (pinfunction "-IN_6") (pintype "input"))
      (node (ref "R14") (pin "1") (pinfunction "1_1") (pintype "passive"))
      (node (ref "R15") (pin "2") (pinfunction "2_2") (pintype "passive"))
    )
    (net (code "49") (name "Net-(IC6B-OUT)") (class "Default")
      (node (ref "IC6") (pin "7") (pinfunction "OUT_7") (pintype "output"))
      (node (ref "R13") (pin "1") (pinfunction "1_1") (pintype "passive"))
      (node (ref "R14") (pin "2") (pinfunction "2_2") (pintype "passive"))
    )
    (net (code "50") (name "Net-(IC6C--IN)") (class "Default")
      (node (ref "IC6") (pin "9") (pinfunction "-IN_9") (pintype "input"))
      (node (ref "R11") (pin "1") (pinfunction "1_1") (pintype "passive"))
      (node (ref "R12") (pin "2") (pinfunction "2_2") (pintype "passive"))
    )
    (net (code "51") (name "Net-(IC6C-OUT)") (class "Default")
      (node (ref "IC6") (pin "8") (pinfunction "OUT_8") (pintype "output"))
      (node (ref "R10") (pin "1") (pinfunction "1_1") (pintype "passive"))
      (node (ref "R11") (pin "2") (pinfunction "2_2") (pintype "passive"))
    )
    (net (code "52") (name "Net-(IC6D--IN)") (class "Default")
      (node (ref "IC6") (pin "13") (pinfunction "-IN_13") (pintype "input"))
      (node (ref "R8") (pin "1") (pinfunction "1_1") (pintype "passive"))
      (node (ref "R9") (pin "2") (pinfunction "2_2") (pintype "passive"))
    )
    (net (code "53") (name "Net-(IC6D-OUT)") (class "Default")
      (node (ref "IC6") (pin "14") (pinfunction "OUT_14") (pintype "output"))
      (node (ref "R7") (pin "1") (pinfunction "1_1") (pintype "passive"))
      (node (ref "R8") (pin "2") (pinfunction "2_2") (pintype "passive"))
    )
    (net (code "54") (name "Net-(IC7-OUT0)") (class "Default")
      (node (ref "IC7") (pin "35") (pinfunction "OUT0_35") (pintype "output"))
      (node (ref "IC8") (pin "3") (pinfunction "+IN_3") (pintype "input"))
    )
    (net (code "55") (name "Net-(IC7-OUT1)") (class "Default")
      (node (ref "IC7") (pin "33") (pinfunction "OUT1_33") (pintype "output"))
      (node (ref "IC8") (pin "5") (pinfunction "+IN_5") (pintype "input"))
    )
    (net (code "56") (name "Net-(IC7-OUT2)") (class "Default")
      (node (ref "IC7") (pin "31") (pinfunction "OUT2_31") (pintype "output"))
      (node (ref "IC8") (pin "10") (pinfunction "+IN_10") (pintype "input"))
    )
    (net (code "57") (name "Net-(IC7-OUT3)") (class "Default")
      (node (ref "IC7") (pin "28") (pinfunction "OUT3_28") (pintype "output"))
      (node (ref "IC8") (pin "12") (pinfunction "+IN_12") (pintype "input"))
    )
    (net (code "58") (name "Net-(IC8A--IN)") (class "Default")
      (node (ref "IC8") (pin "2") (pinfunction "-IN_2") (pintype "input"))
      (node (ref "R20") (pin "1") (pinfunction "1_1") (pintype "passive"))
      (node (ref "R21") (pin "2") (pinfunction "2_2") (pintype "passive"))
    )
    (net (code "59") (name "Net-(IC8A-OUT)") (class "Default")
      (node (ref "IC8") (pin "1") (pinfunction "OUT_1") (pintype "output"))
      (node (ref "R19") (pin "1") (pinfunction "1_1") (pintype "passive"))
      (node (ref "R20") (pin "2") (pinfunction "2_2") (pintype "passive"))
    )
    (net (code "60") (name "Net-(IC8B--IN)") (class "Default")
      (node (ref "IC8") (pin "6") (pinfunction "-IN_6") (pintype "input"))
      (node (ref "R23") (pin "1") (pinfunction "1_1") (pintype "passive"))
      (node (ref "R24") (pin "2") (pinfunction "2_2") (pintype "passive"))
    )
    (net (code "61") (name "Net-(IC8B-OUT)") (class "Default")
      (node (ref "IC8") (pin "7") (pinfunction "OUT_7") (pintype "output"))
      (node (ref "R22") (pin "1") (pinfunction "1_1") (pintype "passive"))
      (node (ref "R23") (pin "2") (pinfunction "2_2") (pintype "passive"))
    )
    (net (code "62") (name "Net-(IC8C--IN)") (class "Default")
      (node (ref "IC8") (pin "9") (pinfunction "-IN_9") (pintype "input"))
      (node (ref "R26") (pin "1") (pinfunction "1_1") (pintype "passive"))
      (node (ref "R27") (pin "2") (pinfunction "2_2") (pintype "passive"))
    )
    (net (code "63") (name "Net-(IC8C-OUT)") (class "Default")
      (node (ref "IC8") (pin "8") (pinfunction "OUT_8") (pintype "output"))
      (node (ref "R25") (pin "1") (pinfunction "1_1") (pintype "passive"))
      (node (ref "R26") (pin "2") (pinfunction "2_2") (pintype "passive"))
    )
    (net (code "64") (name "Net-(IC8D--IN)") (class "Default")
      (node (ref "IC8") (pin "13") (pinfunction "-IN_13") (pintype "input"))
      (node (ref "R29") (pin "1") (pinfunction "1_1") (pintype "passive"))
      (node (ref "R30") (pin "2") (pinfunction "2_2") (pintype "passive"))
    )
    (net (code "65") (name "Net-(IC8D-OUT)") (class "Default")
      (node (ref "IC8") (pin "14") (pinfunction "OUT_14") (pintype "output"))
      (node (ref "R28") (pin "1") (pinfunction "1_1") (pintype "passive"))
      (node (ref "R29") (pin "2") (pinfunction "2_2") (pintype "passive"))
    )
    (net (code "66") (name "Net-(IC9A-C1+)") (class "Default")
      (node (ref "C6") (pin "1") (pinfunction "1_1") (pintype "passive"))
      (node (ref "IC9") (pin "1") (pinfunction "C1+_1") (pintype "bidirectional"))
    )
    (net (code "67") (name "Net-(IC9A-C1-)") (class "Default")
      (node (ref "C6") (pin "2") (pinfunction "2_2") (pintype "passive"))
      (node (ref "IC9") (pin "3") (pinfunction "C1-_3") (pintype "bidirectional"))
    )
    (net (code "68") (name "Net-(IC9A-C2+)") (class "Default")
      (node (ref "C7") (pin "1") (pinfunction "1_1") (pintype "passive"))
      (node (ref "IC9") (pin "4") (pinfunction "C2+_4") (pintype "bidirectional"))
    )
    (net (code "69") (name "Net-(IC9A-C2-)") (class "Default")
      (node (ref "C7") (pin "2") (pinfunction "2_2") (pintype "passive"))
      (node (ref "IC9") (pin "5") (pinfunction "C2-_5") (pintype "bidirectional"))
    )
    (net (code "70") (name "Net-(IC9A-R2IN)") (class "Default")
      (node (ref "IC9") (pin "8") (pinfunction "R2IN_8") (pintype "input"))
      (node (ref "SL3") (pin "2") (pinfunction "2_2") (pintype "passive"))
    )
    (net (code "71") (name "Net-(IC9A-T1OUT)") (class "Default")
      (node (ref "IC9") (pin "14") (pinfunction "T1OUT_14") (pintype "output"))
      (node (ref "SL3") (pin "3") (pinfunction "3_3") (pintype "passive"))
    )
    (net (code "72") (name "Net-(IC9A-V+)") (class "Default")
      (node (ref "C8") (pin "2") (pinfunction "2_2") (pintype "passive"))
      (node (ref "IC9") (pin "2") (pinfunction "V+_2") (pintype "bidirectional"))
    )
    (net (code "73") (name "Net-(IC9A-V-)") (class "Default")
      (node (ref "C9") (pin "1") (pinfunction "1_1") (pintype "passive"))
      (node (ref "IC9") (pin "6") (pinfunction "V-_6") (pintype "bidirectional"))
    )
    (net (code "74") (name "Net-(JP2-Pad1)") (class "Default")
      (node (ref "JP2") (pin "1") (pinfunction "1_1") (pintype "passive"))
      (node (ref "R5") (pin "1") (pinfunction "1_1") (pintype "passive"))
      (node (ref "R6") (pin "2") (pinfunction "2_2") (pintype "passive"))
    )
    (net (code "75") (name "Net-(R7-Pad2)") (class "Default")
      (node (ref "R7") (pin "2") (pinfunction "2_2") (pintype "passive"))
      (node (ref "X21") (pin "1") (pinfunction "1_1") (pintype "passive"))
    )
    (net (code "76") (name "Net-(R10-Pad2)") (class "Default")
      (node (ref "R10") (pin "2") (pinfunction "2_2") (pintype "passive"))
      (node (ref "X22") (pin "1") (pinfunction "1_1") (pintype "passive"))
    )
    (net (code "77") (name "Net-(R13-Pad2)") (class "Default")
      (node (ref "R13") (pin "2") (pinfunction "2_2") (pintype "passive"))
      (node (ref "X23") (pin "1") (pinfunction "1_1") (pintype "passive"))
    )
    (net (code "78") (name "Net-(R16-Pad2)") (class "Default")
      (node (ref "R16") (pin "2") (pinfunction "2_2") (pintype "passive"))
      (node (ref "X24") (pin "1") (pinfunction "1_1") (pintype "passive"))
    )
    (net (code "79") (name "Net-(R19-Pad2)") (class "Default")
      (node (ref "R19") (pin "2") (pinfunction "2_2") (pintype "passive"))
      (node (ref "X25") (pin "1") (pinfunction "1_1") (pintype "passive"))
    )
    (net (code "80") (name "Net-(R22-Pad2)") (class "Default")
      (node (ref "R22") (pin "2") (pinfunction "2_2") (pintype "passive"))
      (node (ref "X26") (pin "1") (pinfunction "1_1") (pintype "passive"))
    )
    (net (code "81") (name "Net-(R25-Pad2)") (class "Default")
      (node (ref "R25") (pin "2") (pinfunction "2_2") (pintype "passive"))
      (node (ref "X27") (pin "1") (pinfunction "1_1") (pintype "passive"))
    )
    (net (code "82") (name "Net-(R28-Pad2)") (class "Default")
      (node (ref "R28") (pin "2") (pinfunction "2_2") (pintype "passive"))
      (node (ref "X28") (pin "1") (pinfunction "1_1") (pintype "passive"))
    )
    (net (code "83") (name "VDD") (class "Default")
      (node (ref "C11") (pin "1") (pinfunction "1_1") (pintype "passive"))
      (node (ref "C12") (pin "1") (pinfunction "1_1") (pintype "passive"))
      (node (ref "C13") (pin "1") (pinfunction "1_1") (pintype "passive"))
      (node (ref "C19") (pin "2") (pinfunction "2_2") (pintype "passive"))
      (node (ref "C2") (pin "1") (pinfunction "1_1") (pintype "passive"))
      (node (ref "C218") (pin "2") (pinfunction "2_2") (pintype "passive"))
      (node (ref "C8") (pin "1") (pinfunction "1_1") (pintype "passive"))
      (node (ref "IC3") (pin "5") (pinfunction "EN_5") (pintype "bidirectional"))
      (node (ref "IC3") (pin "8") (pinfunction "VCCB_8") (pintype "bidirectional"))
      (node (ref "IC4") (pin "3") (pinfunction "VO_3") (pintype "passive"))
      (node (ref "IC5") (pin "11") (pinfunction "EDGE/~{LEVEL}_11") (pintype "input"))
      (node (ref "IC5") (pin "13") (pinfunction "V+_13") (pintype "power_in"))
      (node (ref "IC5") (pin "17") (pinfunction "SER/~{PAR}_17") (pintype "input"))
      (node (ref "IC5") (pin "27") (pinfunction "CE_27") (pintype "input"))
      (node (ref "IC5") (pin "36") (pinfunction "V+_36") (pintype "power_in"))
      (node (ref "IC5") (pin "7") (pinfunction "LOAD_7") (pintype "input"))
      (node (ref "IC6") (pin "4") (pinfunction "V+_4") (pintype "power_in"))
      (node (ref "IC7") (pin "11") (pinfunction "EDGE/~{LEVEL}_11") (pintype "input"))
      (node (ref "IC7") (pin "13") (pinfunction "V+_13") (pintype "power_in"))
      (node (ref "IC7") (pin "17") (pinfunction "SER/~{PAR}_17") (pintype "input"))
      (node (ref "IC7") (pin "27") (pinfunction "CE_27") (pintype "input"))
      (node (ref "IC7") (pin "36") (pinfunction "V+_36") (pintype "power_in"))
      (node (ref "IC7") (pin "7") (pinfunction "LOAD_7") (pintype "input"))
      (node (ref "IC8") (pin "4") (pinfunction "V+_4") (pintype "power_in"))
      (node (ref "IC9") (pin "16") (pinfunction "VCC_16") (pintype "power_in"))
      (node (ref "JP1") (pin "2") (pinfunction "2_2") (pintype "passive"))
      (node (ref "JP2") (pin "3") (pinfunction "3_3") (pintype "passive"))
      (node (ref "JP8") (pin "5") (pinfunction "5_5") (pintype "passive"))
      (node (ref "R3") (pin "1") (pinfunction "1_1") (pintype "passive"))
      (node (ref "R4") (pin "1") (pinfunction "1_1") (pintype "passive"))
      (node (ref "R5") (pin "2") (pinfunction "2_2") (pintype "passive"))
    )
    (net (code "84") (name "VSS") (class "Default")
      (node (ref "C15") (pin "1") (pinfunction "1_1") (pintype "passive"))
      (node (ref "C16") (pin "1") (pinfunction "1_1") (pintype "passive"))
      (node (ref "C17") (pin "1") (pinfunction "1_1") (pintype "passive"))
      (node (ref "C19") (pin "1") (pinfunction "1_1") (pintype "passive"))
      (node (ref "C218") (pin "1") (pinfunction "1_1") (pintype "passive"))
      (node (ref "IC5") (pin "19") (pinfunction "V-_19") (pintype "power_in"))
      (node (ref "IC5") (pin "30") (pinfunction "V-_30") (pintype "power_in"))
      (node (ref "IC6") (pin "11") (pinfunction "V-_11") (pintype "power_in"))
      (node (ref "IC7") (pin "19") (pinfunction "V-_19") (pintype "power_in"))
      (node (ref "IC7") (pin "30") (pinfunction "V-_30") (pintype "power_in"))
      (node (ref "IC8") (pin "11") (pinfunction "V-_11") (pintype "power_in"))
      (node (ref "JP8") (pin "1") (pinfunction "1_1") (pintype "passive"))
      (node (ref "L2") (pin "2") (pinfunction "2_2") (pintype "passive"))
    )
    (net (code "85") (name "unconnected-(DC1-+VOUT-Pad6)") (class "Default")
      (node (ref "DC1") (pin "6") (pinfunction "+VOUT_6") (pintype "passive"))
    )
    (net (code "86") (name "unconnected-(IC1-ADC6-Pad19)") (class "Default")
      (node (ref "IC1") (pin "19") (pinfunction "ADC6_19") (pintype "bidirectional"))
    )
    (net (code "87") (name "unconnected-(IC1-ADC7-Pad22)") (class "Default")
      (node (ref "IC1") (pin "22") (pinfunction "ADC7_22") (pintype "bidirectional"))
    )
    (net (code "88") (name "unconnected-(IC1-PB0(ICP)-Pad12)") (class "Default")
      (node (ref "IC1") (pin "12") (pinfunction "PB0(ICP)_12") (pintype "bidirectional"))
    )
    (net (code "89") (name "unconnected-(IC1-PB1(OC1A)-Pad13)") (class "Default")
      (node (ref "IC1") (pin "13") (pinfunction "PB1(OC1A)_13") (pintype "bidirectional"))
    )
    (net (code "90") (name "unconnected-(IC1-PC1(ADC1)-Pad24)") (class "Default")
      (node (ref "IC1") (pin "24") (pinfunction "PC1(ADC1)_24") (pintype "bidirectional"))
    )
    (net (code "91") (name "unconnected-(IC1-PC2(ADC2)-Pad25)") (class "Default")
      (node (ref "IC1") (pin "25") (pinfunction "PC2(ADC2)_25") (pintype "bidirectional"))
    )
    (net (code "92") (name "unconnected-(IC1-PC3(ADC3)-Pad26)") (class "Default")
      (node (ref "IC1") (pin "26") (pinfunction "PC3(ADC3)_26") (pintype "bidirectional"))
    )
    (net (code "93") (name "unconnected-(IC1-PD3(INT1)-Pad1)") (class "Default")
      (node (ref "IC1") (pin "1") (pinfunction "PD3(INT1)_1") (pintype "bidirectional"))
    )
    (net (code "94") (name "unconnected-(IC1-PD5(T1)-Pad9)") (class "Default")
      (node (ref "IC1") (pin "9") (pinfunction "PD5(T1)_9") (pintype "bidirectional"))
    )
    (net (code "95") (name "unconnected-(IC1-PD6(AIN0)-Pad10)") (class "Default")
      (node (ref "IC1") (pin "10") (pinfunction "PD6(AIN0)_10") (pintype "bidirectional"))
    )
    (net (code "96") (name "unconnected-(IC1-PD7(AIN1)-Pad11)") (class "Default")
      (node (ref "IC1") (pin "11") (pinfunction "PD7(AIN1)_11") (pintype "bidirectional"))
    )
    (net (code "97") (name "unconnected-(IC7-D1{slash}SEROUT-Pad1)") (class "Default")
      (node (ref "IC7") (pin "1") (pinfunction "D1/SEROUT_1") (pintype "bidirectional"))
    )
    (net (code "98") (name "unconnected-(IC9A-R1OUT-Pad12)") (class "Default")
      (node (ref "IC9") (pin "12") (pinfunction "R1OUT_12") (pintype "output"))
    )
    (net (code "99") (name "unconnected-(IC9A-T2OUT-Pad7)") (class "Default")
      (node (ref "IC9") (pin "7") (pinfunction "T2OUT_7") (pintype "output"))
    )
    (net (code "100") (name "unconnected-(JP7-Pad4)") (class "Default")
      (node (ref "JP7") (pin "4") (pinfunction "4_4") (pintype "passive"))
    )
    (net (code "101") (name "unconnected-(X1-Pad-2)") (class "Default")
      (node (ref "X1") (pin "-2") (pinfunction "-2_-2") (pintype "passive"))
    )
  )
)
